# mcu.net
KiCad netlist of a schematic drawn in Altium Designer
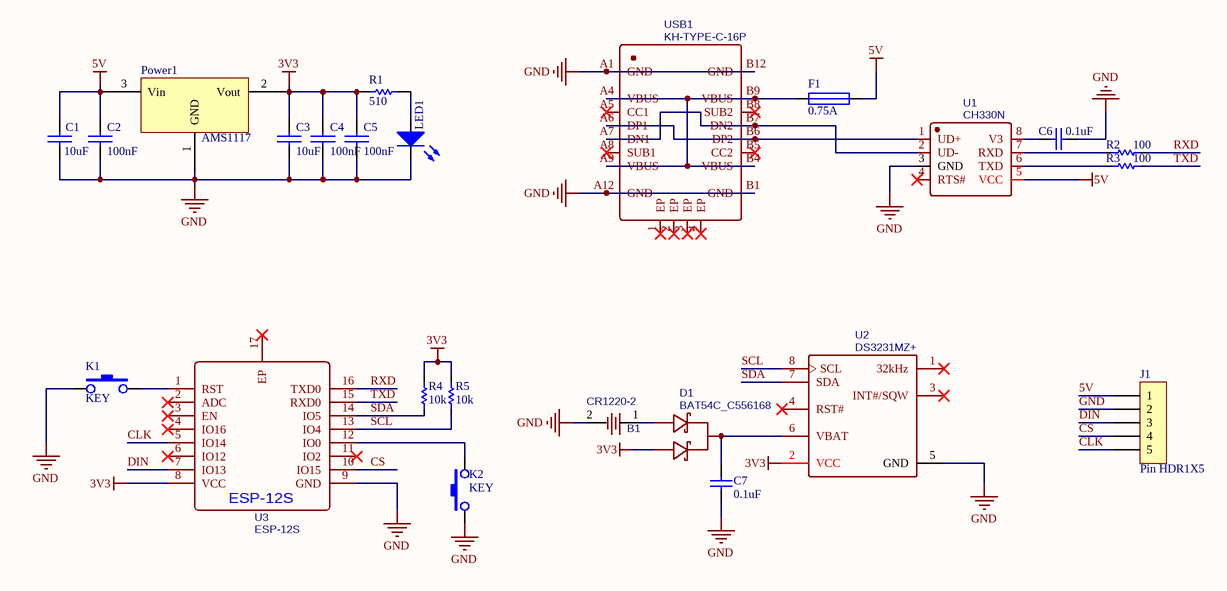
[diagram p0: mcu.SchDoc]

(export (version "E")
  (design (tool "Eeschema 10.0.6"))
  (components
    (comp (ref "B1")
      (value "CR1220-2")
      (footprint "CR1220")
      (fields (field (name "BOM_SUPPLIER PART") "C70381"))
      (libsource (lib "altium-import") (part "root_2_CR1220-2_"))
    )
    (comp (ref "C1")
      (value "10uF")
      (footprint "0805c")
      (description "无极性电容")
      (libsource (lib "电容") (part "CAP"))
    )
    (comp (ref "C2")
      (value "100nF")
      (footprint "0603C")
      (description "无极性电容")
      (libsource (lib "电容") (part "CAP"))
    )
    (comp (ref "C3")
      (value "10uF")
      (footprint "0805C")
      (description "无极性电容")
      (libsource (lib "电容") (part "CAP"))
    )
    (comp (ref "C4")
      (value "100nF")
      (footprint "0603C")
      (description "无极性电容")
      (libsource (lib "电容") (part "CAP"))
    )
    (comp (ref "C5")
      (value "100nF")
      (footprint "0603C")
      (description "无极性电容")
      (libsource (lib "电容") (part "CAP"))
    )
    (comp (ref "C6")
      (value "0.1uF")
      (footprint "0603C")
      (description "Capacitor")
      (fields (field (name "PUBLISHER") "Altium Limited"))
      (libsource (lib "MyComponents_v2.5") (part "Cap"))
    )
    (comp (ref "C7")
      (value "0.1uF")
      (footprint "0603C")
      (description "Capacitor")
      (fields (field (name "PUBLISHER") "Altium Limited"))
      (libsource (lib "MyComponents_v2.5") (part "Cap"))
    )
    (comp (ref "D1")
      (value "BAT54C_C556168")
      (footprint "BAT54C")
      (fields
        (field (name "BOM_SUPPLIER PART") "C556168")
        (field (name "BOM_MANUFACTURER PART") "BAT54C")
        (field (name "CONTRIBUTOR") "LCSC")
      )
      (libsource (lib "altium-import") (part "root_0_BAT54C_C556168_"))
    )
    (comp (ref "F1") (value "0.75A") (footprint "1206") (libsource (lib "MyComponents_v2.5") (part "FUSE")))
    (comp (ref "J1")
      (value "Pin HDR1X5")
      (footprint "Pin HDR1X5/2mm-W")
      (libsource (lib "排针") (part "Pin HDR1X5"))
    )
    (comp (ref "K1") (value "KEY") (footprint "DIP-3X6X5_C") (libsource (lib "轻触开关") (part "KEY")))
    (comp (ref "K2") (value "KEY") (footprint "DIP-3X6X5_C") (libsource (lib "轻触开关") (part "KEY")))
    (comp (ref "LED1")
      (value "LED_RED")
      (footprint "0603LED_R")
      (description "Typical RED, GREEN, YELLOW, AMBER GaAs LED")
      (fields (field (name "PUBLISHER") "Altium Limited"))
      (libsource (lib "MyComponents_v2.5") (part "LED"))
    )
    (comp (ref "Power1")
      (value "AMS1117")
      (footprint "SOT223")
      (description "三端稳压芯片")
      (libsource (lib "电源芯片") (part "AMS1117"))
    )
    (comp (ref "R1") (value "510") (footprint "0603R") (libsource (lib "电阻") (part "RES")))
    (comp (ref "R2")
      (value "100")
      (footprint "0603R")
      (description "Resistor")
      (fields (field (name "PUBLISHER") "Altium Limited"))
      (libsource (lib "MyComponents_v2.5") (part "Res1"))
    )
    (comp (ref "R3")
      (value "100")
      (footprint "0603R")
      (description "Resistor")
      (fields (field (name "PUBLISHER") "Altium Limited"))
      (libsource (lib "MyComponents_v2.5") (part "Res1"))
    )
    (comp (ref "R4")
      (value "10k")
      (footprint "0603R")
      (description "Resistor")
      (fields (field (name "PUBLISHER") "Altium Limited"))
      (libsource (lib "MyComponents_v2.5") (part "Res1"))
    )
    (comp (ref "R5")
      (value "10k")
      (footprint "0603R")
      (description "Resistor")
      (fields (field (name "PUBLISHER") "Altium Limited"))
      (libsource (lib "MyComponents_v2.5") (part "Res1"))
    )
    (comp (ref "U1")
      (value "CH330N")
      (footprint "CH340N")
      (fields (field (name "BOM_SUPPLIER PART") "C108996"))
      (libsource (lib "altium-import") (part "root_0_CH330N_"))
    )
    (comp (ref "U2")
      (value "DS3231MZ+")
      (footprint "DS3231MZ+")
      (fields (field (name "BOM_SUPPLIER PART") "C107410"))
      (libsource (lib "altium-import") (part "root_0_DS3231MZ+_"))
    )
    (comp (ref "U3")
      (value "ESP-12S")
      (footprint "ESP-12S")
      (fields (field (name "BOM_SUPPLIER PART") "C82898") (field (name "CONTRIBUTOR") "LCSC"))
      (libsource (lib "altium-import") (part "root_0_ESP-12S_"))
    )
    (comp (ref "USB1")
      (value "KH-TYPE-C-16P")
      (footprint "Type-c")
      (fields (field (name "BOM_SUPPLIER PART") "C709357") (field (name "CONTRIBUTOR") "LCSC"))
      (libsource (lib "altium-import") (part "root_0_KH-TYPE-C-16P_"))
    )
  )
  (nets
    (net (code "1") (name "/CLK") (class "Default")
      (node (ref "J1") (pin "5") (pinfunction "5_5") (pintype "passive"))
      (node (ref "U3") (pin "5") (pinfunction "IO14_5") (pintype "passive"))
    )
    (net (code "2") (name "/CS") (class "Default")
      (node (ref "J1") (pin "4") (pinfunction "4_4") (pintype "passive"))
      (node (ref "U3") (pin "10") (pinfunction "IO15_10") (pintype "passive"))
    )
    (net (code "3") (name "/DIN") (class "Default")
      (node (ref "J1") (pin "3") (pinfunction "3_3") (pintype "passive"))
      (node (ref "U3") (pin "7") (pinfunction "IO13_7") (pintype "passive"))
    )
    (net (code "4") (name "/RXD") (class "Default")
      (node (ref "R2") (pin "2") (pinfunction "2_2") (pintype "passive"))
      (node (ref "U3") (pin "16") (pinfunction "TXD0_16") (pintype "passive"))
    )
    (net (code "5") (name "/SCL") (class "Default")
      (node (ref "R5") (pin "1") (pinfunction "1_1") (pintype "passive"))
      (node (ref "U2") (pin "8") (pinfunction "SCL_8") (pintype "passive"))
      (node (ref "U3") (pin "13") (pinfunction "IO4_13") (pintype "passive"))
    )
    (net (code "6") (name "/SDA") (class "Default")
      (node (ref "R4") (pin "1") (pinfunction "1_1") (pintype "passive"))
      (node (ref "U2") (pin "7") (pinfunction "SDA_7") (pintype "passive"))
      (node (ref "U3") (pin "14") (pinfunction "IO5_14") (pintype "passive"))
    )
    (net (code "7") (name "/TXD") (class "Default")
      (node (ref "R3") (pin "2") (pinfunction "2_2") (pintype "passive"))
      (node (ref "U3") (pin "15") (pinfunction "RXD0_15") (pintype "passive"))
    )
    (net (code "8") (name "3V3") (class "Default")
      (node (ref "C3") (pin "2") (pinfunction "2_2") (pintype "passive"))
      (node (ref "C4") (pin "2") (pinfunction "2_2") (pintype "passive"))
      (node (ref "C5") (pin "2") (pinfunction "2_2") (pintype "passive"))
      (node (ref "D1") (pin "2") (pinfunction "+_2") (pintype "passive"))
      (node (ref "Power1") (pin "2") (pinfunction "Vout_2") (pintype "passive"))
      (node (ref "R1") (pin "1") (pinfunction "1_1") (pintype "passive"))
      (node (ref "R4") (pin "2") (pinfunction "2_2") (pintype "passive"))
      (node (ref "R5") (pin "2") (pinfunction "2_2") (pintype "passive"))
      (node (ref "U2") (pin "2") (pinfunction "VCC_2") (pintype "passive"))
      (node (ref "U3") (pin "8") (pinfunction "VCC_8") (pintype "passive"))
    )
    (net (code "9") (name "5V") (class "Default")
      (node (ref "C1") (pin "2") (pinfunction "2_2") (pintype "passive"))
      (node (ref "C2") (pin "2") (pinfunction "2_2") (pintype "passive"))
      (node (ref "F1") (pin "2") (pinfunction "2_2") (pintype "passive"))
      (node (ref "J1") (pin "1") (pinfunction "1_1") (pintype "passive"))
      (node (ref "Power1") (pin "3") (pinfunction "Vin_3") (pintype "passive"))
      (node (ref "U1") (pin "5") (pinfunction "VCC_5") (pintype "passive"))
    )
    (net (code "10") (name "GND") (class "Default")
      (node (ref "B1") (pin "2") (pinfunction "2_2") (pintype "passive"))
      (node (ref "C1") (pin "1") (pinfunction "1_1") (pintype "passive"))
      (node (ref "C2") (pin "1") (pinfunction "1_1") (pintype "passive"))
      (node (ref "C3") (pin "1") (pinfunction "1_1") (pintype "passive"))
      (node (ref "C4") (pin "1") (pinfunction "1_1") (pintype "passive"))
      (node (ref "C5") (pin "1") (pinfunction "1_1") (pintype "passive"))
      (node (ref "C6") (pin "2") (pinfunction "2_2") (pintype "passive"))
      (node (ref "C7") (pin "1") (pinfunction "1_1") (pintype "passive"))
      (node (ref "J1") (pin "2") (pinfunction "2_2") (pintype "passive"))
      (node (ref "K1") (pin "1") (pinfunction "1_1") (pintype "passive"))
      (node (ref "K2") (pin "1") (pinfunction "1_1") (pintype "passive"))
      (node (ref "LED1") (pin "2") (pinfunction "2_2") (pintype "passive"))
      (node (ref "Power1") (pin "1") (pinfunction "GND_1") (pintype "passive"))
      (node (ref "U1") (pin "3") (pinfunction "GND_3") (pintype "passive"))
      (node (ref "U2") (pin "5") (pinfunction "GND_5") (pintype "passive"))
      (node (ref "U3") (pin "9") (pinfunction "GND_9") (pintype "passive"))
      (node (ref "USB1") (pin "A1") (pinfunction "GND_A1") (pintype "passive"))
      (node (ref "USB1") (pin "A12") (pinfunction "GND_A12") (pintype "passive"))
      (node (ref "USB1") (pin "B1") (pinfunction "GND_B1") (pintype "passive"))
      (node (ref "USB1") (pin "B12") (pinfunction "GND_B12") (pintype "passive"))
    )
    (net (code "11") (name "Net-(B1-Pad1)") (class "Default")
      (node (ref "B1") (pin "1") (pinfunction "1_1") (pintype "passive"))
      (node (ref "D1") (pin "1") (pinfunction "+_1") (pintype "passive"))
    )
    (net (code "12") (name "Net-(D1--)") (class "Default")
      (node (ref "C7") (pin "2") (pinfunction "2_2") (pintype "passive"))
      (node (ref "D1") (pin "3") (pinfunction "-_3") (pintype "passive"))
      (node (ref "U2") (pin "6") (pinfunction "VBAT_6") (pintype "passive"))
    )
    (net (code "13") (name "Net-(F1-Pad1)") (class "Default")
      (node (ref "F1") (pin "1") (pinfunction "1_1") (pintype "passive"))
      (node (ref "USB1") (pin "A4") (pinfunction "VBUS_A4") (pintype "passive"))
      (node (ref "USB1") (pin "A9") (pinfunction "VBUS_A9") (pintype "passive"))
      (node (ref "USB1") (pin "B4") (pinfunction "VBUS_B4") (pintype "passive"))
      (node (ref "USB1") (pin "B9") (pinfunction "VBUS_B9") (pintype "passive"))
    )
    (net (code "14") (name "Net-(LED1-Pad1)") (class "Default")
      (node (ref "LED1") (pin "1") (pinfunction "1_1") (pintype "passive"))
      (node (ref "R1") (pin "2") (pinfunction "2_2") (pintype "passive"))
    )
    (net (code "15") (name "Net-(U1-RXD)") (class "Default")
      (node (ref "R2") (pin "1") (pinfunction "1_1") (pintype "passive"))
      (node (ref "U1") (pin "7") (pinfunction "RXD_7") (pintype "passive"))
    )
    (net (code "16") (name "Net-(U1-TXD)") (class "Default")
      (node (ref "R3") (pin "1") (pinfunction "1_1") (pintype "passive"))
      (node (ref "U1") (pin "6") (pinfunction "TXD_6") (pintype "passive"))
    )
    (net (code "17") (name "Net-(U1-UD+)") (class "Default")
      (node (ref "U1") (pin "1") (pinfunction "UD+_1") (pintype "passive"))
      (node (ref "USB1") (pin "A6") (pinfunction "DP1_A6") (pintype "passive"))
      (node (ref "USB1") (pin "B6") (pinfunction "DP2_B6") (pintype "passive"))
    )
    (net (code "18") (name "Net-(U1-UD-)") (class "Default")
      (node (ref "U1") (pin "2") (pinfunction "UD-_2") (pintype "passive"))
      (node (ref "USB1") (pin "A7") (pinfunction "DN1_A7") (pintype "passive"))
      (node (ref "USB1") (pin "B7") (pinfunction "DN2_B7") (pintype "passive"))
    )
    (net (code "19") (name "Net-(U1-V3)") (class "Default")
      (node (ref "C6") (pin "1") (pinfunction "1_1") (pintype "passive"))
      (node (ref "U1") (pin "8") (pinfunction "V3_8") (pintype "passive"))
    )
    (net (code "20") (name "Net-(U3-IO0)") (class "Default")
      (node (ref "K2") (pin "3") (pinfunction "3_3") (pintype "passive"))
      (node (ref "U3") (pin "12") (pinfunction "IO0_12") (pintype "passive"))
    )
    (net (code "21") (name "Net-(U3-RST)") (class "Default")
      (node (ref "K1") (pin "3") (pinfunction "3_3") (pintype "passive"))
      (node (ref "U3") (pin "1") (pinfunction "RST_1") (pintype "passive"))
    )
    (net (code "22") (name "unconnected-(U1-RTS#-Pad4)") (class "Default")
      (node (ref "U1") (pin "4") (pinfunction "RTS#_4") (pintype "passive+no_connect"))
    )
    (net (code "23") (name "unconnected-(U2-32kHz-Pad1)") (class "Default")
      (node (ref "U2") (pin "1") (pinfunction "32kHz_1") (pintype "passive+no_connect"))
    )
    (net (code "24") (name "unconnected-(U2-INT#{slash}SQW-Pad3)") (class "Default")
      (node (ref "U2") (pin "3") (pinfunction "INT#/SQW_3") (pintype "passive+no_connect"))
    )
    (net (code "25") (name "unconnected-(U2-RST#-Pad4)") (class "Default")
      (node (ref "U2") (pin "4") (pinfunction "RST#_4") (pintype "passive+no_connect"))
    )
    (net (code "26") (name "unconnected-(U3-ADC-Pad2)") (class "Default")
      (node (ref "U3") (pin "2") (pinfunction "ADC_2") (pintype "passive+no_connect"))
    )
    (net (code "27") (name "unconnected-(U3-EN-Pad3)") (class "Default")
      (node (ref "U3") (pin "3") (pinfunction "EN_3") (pintype "passive+no_connect"))
    )
    (net (code "28") (name "unconnected-(U3-EP-Pad17)") (class "Default")
      (node (ref "U3") (pin "17") (pinfunction "EP_17") (pintype "passive+no_connect"))
    )
    (net (code "29") (name "unconnected-(U3-IO2-Pad11)") (class "Default")
      (node (ref "U3") (pin "11") (pinfunction "IO2_11") (pintype "passive+no_connect"))
    )
    (net (code "30") (name "unconnected-(U3-IO12-Pad6)") (class "Default")
      (node (ref "U3") (pin "6") (pinfunction "IO12_6") (pintype "passive+no_connect"))
    )
    (net (code "31") (name "unconnected-(U3-IO16-Pad4)") (class "Default")
      (node (ref "U3") (pin "4") (pinfunction "IO16_4") (pintype "passive+no_connect"))
    )
    (net (code "32") (name "unconnected-(USB1-CC1-PadA5)") (class "Default")
      (node (ref "USB1") (pin "A5") (pinfunction "CC1_A5") (pintype "passive+no_connect"))
    )
    (net (code "33") (name "unconnected-(USB1-CC2-PadB5)") (class "Default")
      (node (ref "USB1") (pin "B5") (pinfunction "CC2_B5") (pintype "passive+no_connect"))
    )
    (net (code "34") (name "unconnected-(USB1-EP-Pad1)") (class "Default")
      (node (ref "USB1") (pin "1") (pinfunction "EP_1") (pintype "passive+no_connect"))
    )
    (net (code "35") (name "unconnected-(USB1-EP-Pad2)") (class "Default")
      (node (ref "USB1") (pin "2") (pinfunction "EP_2") (pintype "passive+no_connect"))
    )
    (net (code "36") (name "unconnected-(USB1-EP-Pad3)") (class "Default")
      (node (ref "USB1") (pin "3") (pinfunction "EP_3") (pintype "passive+no_connect"))
    )
    (net (code "37") (name "unconnected-(USB1-EP-Pad4)") (class "Default")
      (node (ref "USB1") (pin "4") (pinfunction "EP_4") (pintype "passive+no_connect"))
    )
    (net (code "38") (name "unconnected-(USB1-SUB1-PadA8)") (class "Default")
      (node (ref "USB1") (pin "A8") (pinfunction "SUB1_A8") (pintype "passive+no_connect"))
    )
    (net (code "39") (name "unconnected-(USB1-SUB2-PadB8)") (class "Default")
      (node (ref "USB1") (pin "B8") (pinfunction "SUB2_B8") (pintype "passive+no_connect"))
    )
  )
)
